# mySensors.net
KiCad netlist of a schematic drawn in EAGLE
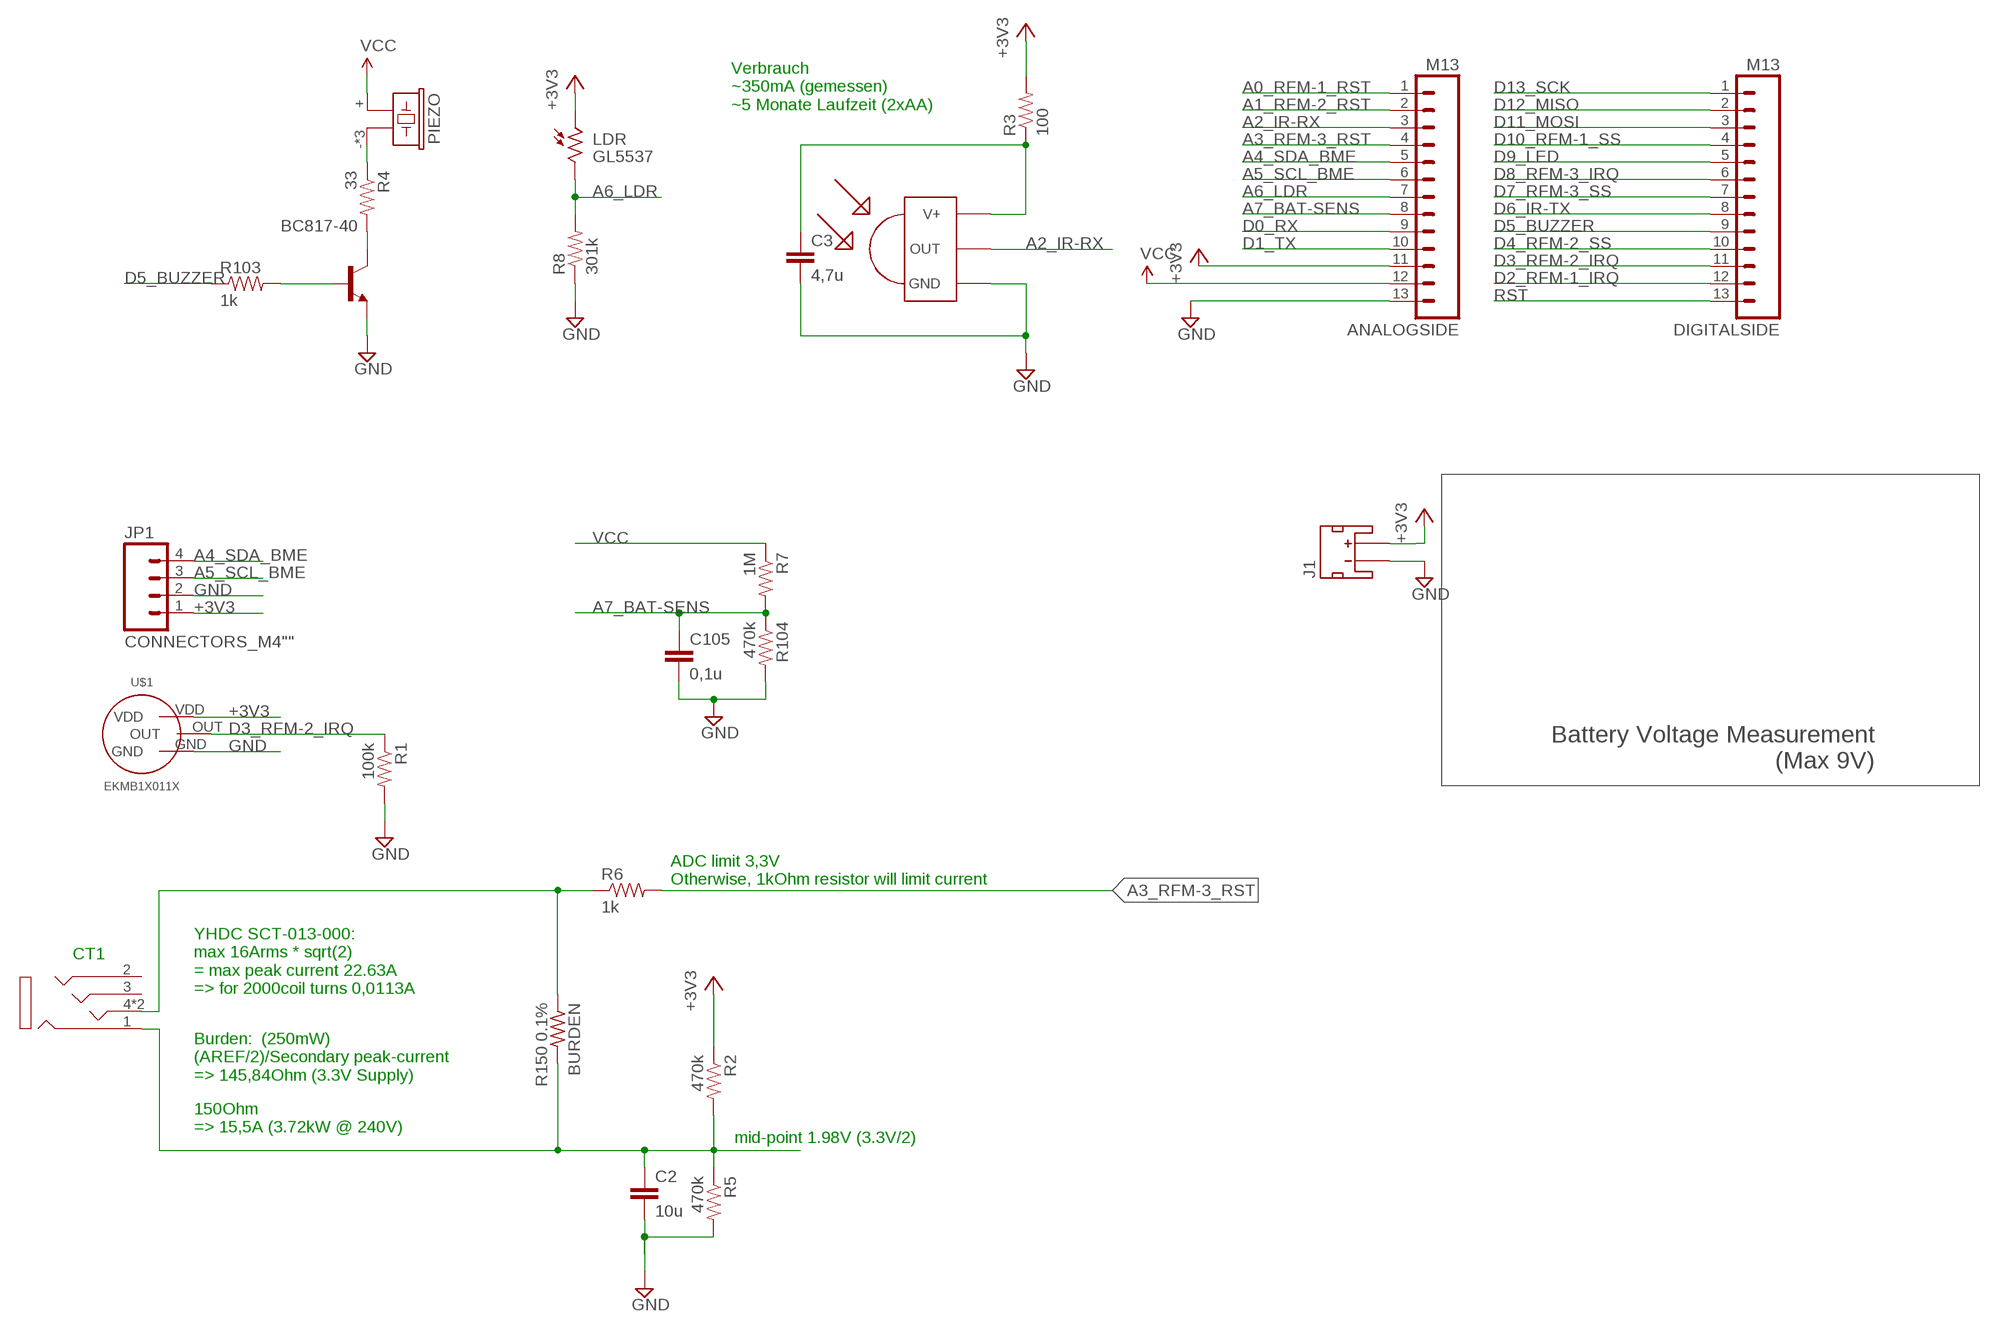
[diagram p0: schematic, sheet 1]

(export (version "E")
  (design (tool "Eeschema 10.0.6"))
  (components
    (comp (ref "ANALOGSIDE")
      (value "M13")
      (footprint "eagle-import:1X13")
      (libsource (lib "eagle-import") (part "M13"))
    )
    (comp (ref "BC817-40")
      (value "BC817-40-NPN-SOT23-BEC")
      (footprint "eagle-import:SOT23-BEC")
      (libsource (lib "eagle-import") (part "-NPN-SOT23-BECBC817-40"))
    )
    (comp (ref "BURDEN")
      (value "R150 0.1%")
      (footprint "eagle-import:R0805")
      (libsource (lib "eagle-import") (part "R-US_R0805"))
    )
    (comp (ref "C2")
      (value "10u")
      (footprint "eagle-import:0805-CAP")
      (libsource (lib "eagle-import") (part "CAP0805-CAP"))
    )
    (comp (ref "C3")
      (value "4,7u")
      (footprint "eagle-import:0805-CAP")
      (libsource (lib "eagle-import") (part "CAP0805-CAP"))
    )
    (comp (ref "C105")
      (value "0,1u")
      (footprint "eagle-import:0603-CAP")
      (libsource (lib "eagle-import") (part "CAP0603-CAP"))
    )
    (comp (ref "CT1")
      (value "1503_13")
      (footprint "eagle-import:1503-03")
      (libsource (lib "eagle-import") (part "1503_13"))
    )
    (comp (ref "DIGITALSIDE")
      (value "M13")
      (footprint "eagle-import:1X13")
      (libsource (lib "eagle-import") (part "M13"))
    )
    (comp (ref "IR-RX")
      (value "TSOP4836")
      (footprint "eagle-import:TSOP18XX")
      (libsource (lib "eagle-import") (part "TSOP4836"))
    )
    (comp (ref "J1")
      (value "JST_2MM_MALE")
      (footprint "eagle-import:JST-2-SMD")
      (libsource (lib "eagle-import") (part "JST_2MM_MALE"))
    )
    (comp (ref "JP1")
      (value "CONNECTORS_M4\"\"")
      (footprint "eagle-import:CONNECTORS_1X4")
      (libsource (lib "eagle-import") (part "CONNECTORS_M4{dblquote}{dblquote}"))
    )
    (comp (ref "LDR")
      (value "GL5537")
      (footprint "eagle-import:M9960")
      (libsource (lib "eagle-import") (part "M9960_11A"))
    )
    (comp (ref "PIEZO")
      (value "BUZZER-PIEZO_SMD")
      (footprint "eagle-import:BUZZER-PIEZO_SMD")
      (libsource (lib "eagle-import") (part "BUZZER-PIEZO_SMD"))
    )
    (comp (ref "R1")
      (value "100k")
      (footprint "eagle-import:0603-RES")
      (libsource (lib "eagle-import") (part "RESISTOR0603-RES"))
    )
    (comp (ref "R2")
      (value "470k")
      (footprint "eagle-import:0603-RES")
      (libsource (lib "eagle-import") (part "RESISTOR0603-RES"))
    )
    (comp (ref "R3")
      (value "100")
      (footprint "eagle-import:0603-RES")
      (libsource (lib "eagle-import") (part "RESISTOR0603-RES"))
    )
    (comp (ref "R4")
      (value "33")
      (footprint "eagle-import:0603-RES")
      (libsource (lib "eagle-import") (part "RESISTOR0603-RES"))
    )
    (comp (ref "R5")
      (value "470k")
      (footprint "eagle-import:0603-RES")
      (libsource (lib "eagle-import") (part "RESISTOR0603-RES"))
    )
    (comp (ref "R6")
      (value "1k")
      (footprint "eagle-import:0603-RES")
      (libsource (lib "eagle-import") (part "RESISTOR0603-RES"))
    )
    (comp (ref "R7")
      (value "1M")
      (footprint "eagle-import:0603-RES")
      (libsource (lib "eagle-import") (part "RESISTOR0603-RES"))
    )
    (comp (ref "R8")
      (value "301k")
      (footprint "eagle-import:0603-RES")
      (libsource (lib "eagle-import") (part "RESISTOR0603-RES"))
    )
    (comp (ref "R103")
      (value "1k")
      (footprint "eagle-import:0603-RES")
      (libsource (lib "eagle-import") (part "RESISTOR0603-RES"))
    )
    (comp (ref "R104")
      (value "470k")
      (footprint "eagle-import:0603-RES")
      (libsource (lib "eagle-import") (part "RESISTOR0603-RES"))
    )
    (comp (ref "U$1")
      (value "EKMB1X011X")
      (footprint "eagle-import:PIR-PANASONIC-VZ-WL-STANDARD")
      (libsource (lib "eagle-import") (part "EKMB1X011X"))
    )
  )
  (nets
    (net (code "1") (name "+3V3") (class "Default")
      (node (ref "ANALOGSIDE") (pin "11") (pinfunction "11_11") (pintype "passive"))
      (node (ref "J1") (pin "2") (pinfunction "+_2") (pintype "bidirectional"))
      (node (ref "JP1") (pin "1") (pinfunction "1_1") (pintype "passive"))
      (node (ref "LDR") (pin "1") (pinfunction "1_1") (pintype "passive"))
      (node (ref "R2") (pin "1") (pinfunction "1_1") (pintype "passive"))
      (node (ref "R3") (pin "2") (pinfunction "2_2") (pintype "passive"))
      (node (ref "U$1") (pin "VDD") (pinfunction "VDD_VDD") (pintype "bidirectional"))
    )
    (net (code "2") (name "/A0_RFM-1_RST") (class "Default")
      (node (ref "ANALOGSIDE") (pin "1") (pinfunction "1_1") (pintype "passive"))
    )
    (net (code "3") (name "/A1_RFM-2_RST") (class "Default")
      (node (ref "ANALOGSIDE") (pin "2") (pinfunction "2_2") (pintype "passive"))
    )
    (net (code "4") (name "/A2_IR-RX") (class "Default")
      (node (ref "ANALOGSIDE") (pin "3") (pinfunction "3_3") (pintype "passive"))
      (node (ref "IR-RX") (pin "OUT") (pinfunction "OUT_OUT") (pintype "bidirectional"))
    )
    (net (code "5") (name "/A4_SDA_BME") (class "Default")
      (node (ref "ANALOGSIDE") (pin "5") (pinfunction "5_5") (pintype "passive"))
      (node (ref "JP1") (pin "4") (pinfunction "4_4") (pintype "passive"))
    )
    (net (code "6") (name "/A5_SCL_BME") (class "Default")
      (node (ref "ANALOGSIDE") (pin "6") (pinfunction "6_6") (pintype "passive"))
      (node (ref "JP1") (pin "3") (pinfunction "3_3") (pintype "passive"))
    )
    (net (code "7") (name "/A6_LDR") (class "Default")
      (node (ref "ANALOGSIDE") (pin "7") (pinfunction "7_7") (pintype "passive"))
      (node (ref "LDR") (pin "2") (pinfunction "2_2") (pintype "passive"))
      (node (ref "R8") (pin "2") (pinfunction "2_2") (pintype "passive"))
    )
    (net (code "8") (name "/A7_BAT-SENS") (class "Default")
      (node (ref "ANALOGSIDE") (pin "8") (pinfunction "8_8") (pintype "passive"))
      (node (ref "C105") (pin "1") (pinfunction "1_1") (pintype "passive"))
      (node (ref "R104") (pin "1") (pinfunction "1_1") (pintype "passive"))
      (node (ref "R7") (pin "2") (pinfunction "2_2") (pintype "passive"))
    )
    (net (code "9") (name "/D0_RX") (class "Default")
      (node (ref "ANALOGSIDE") (pin "9") (pinfunction "9_9") (pintype "passive"))
    )
    (net (code "10") (name "/D1_TX") (class "Default")
      (node (ref "ANALOGSIDE") (pin "10") (pinfunction "10_10") (pintype "passive"))
    )
    (net (code "11") (name "/D2_RFM-1_IRQ") (class "Default")
      (node (ref "DIGITALSIDE") (pin "12") (pinfunction "12_12") (pintype "passive"))
    )
    (net (code "12") (name "/D3_RFM-2_IRQ") (class "Default")
      (node (ref "DIGITALSIDE") (pin "11") (pinfunction "11_11") (pintype "passive"))
      (node (ref "R1") (pin "1") (pinfunction "1_1") (pintype "passive"))
      (node (ref "U$1") (pin "OUT") (pinfunction "OUT_OUT") (pintype "bidirectional"))
    )
    (net (code "13") (name "/D4_RFM-2_SS") (class "Default")
      (node (ref "DIGITALSIDE") (pin "10") (pinfunction "10_10") (pintype "passive"))
    )
    (net (code "14") (name "/D5_BUZZER") (class "Default")
      (node (ref "DIGITALSIDE") (pin "9") (pinfunction "9_9") (pintype "passive"))
      (node (ref "R103") (pin "1") (pinfunction "1_1") (pintype "passive"))
    )
    (net (code "15") (name "/D6_IR-TX") (class "Default")
      (node (ref "DIGITALSIDE") (pin "8") (pinfunction "8_8") (pintype "passive"))
    )
    (net (code "16") (name "/D7_RFM-3_SS") (class "Default")
      (node (ref "DIGITALSIDE") (pin "7") (pinfunction "7_7") (pintype "passive"))
    )
    (net (code "17") (name "/D8_RFM-3_IRQ") (class "Default")
      (node (ref "DIGITALSIDE") (pin "6") (pinfunction "6_6") (pintype "passive"))
    )
    (net (code "18") (name "/D9_LED") (class "Default")
      (node (ref "DIGITALSIDE") (pin "5") (pinfunction "5_5") (pintype "passive"))
    )
    (net (code "19") (name "/D10_RFM-1_SS") (class "Default")
      (node (ref "DIGITALSIDE") (pin "4") (pinfunction "4_4") (pintype "passive"))
    )
    (net (code "20") (name "/D11_MOSI") (class "Default")
      (node (ref "DIGITALSIDE") (pin "3") (pinfunction "3_3") (pintype "passive"))
    )
    (net (code "21") (name "/D12_MISO") (class "Default")
      (node (ref "DIGITALSIDE") (pin "2") (pinfunction "2_2") (pintype "passive"))
    )
    (net (code "22") (name "/D13_SCK") (class "Default")
      (node (ref "DIGITALSIDE") (pin "1") (pinfunction "1_1") (pintype "passive"))
    )
    (net (code "23") (name "/RST") (class "Default")
      (node (ref "DIGITALSIDE") (pin "13") (pinfunction "13_13") (pintype "passive"))
    )
    (net (code "24") (name "A3_RFM-3_RST") (class "Default")
      (node (ref "ANALOGSIDE") (pin "4") (pinfunction "4_4") (pintype "passive"))
      (node (ref "R6") (pin "2") (pinfunction "2_2") (pintype "passive"))
    )
    (net (code "25") (name "GND") (class "Default")
      (node (ref "ANALOGSIDE") (pin "13") (pinfunction "13_13") (pintype "passive"))
      (node (ref "BC817-40") (pin "E") (pinfunction "E_E") (pintype "passive"))
      (node (ref "C105") (pin "2") (pinfunction "2_2") (pintype "passive"))
      (node (ref "C2") (pin "2") (pinfunction "2_2") (pintype "passive"))
      (node (ref "C3") (pin "2") (pinfunction "2_2") (pintype "passive"))
      (node (ref "IR-RX") (pin "GND") (pinfunction "GND_GND") (pintype "bidirectional"))
      (node (ref "J1") (pin "1") (pinfunction "-_1") (pintype "bidirectional"))
      (node (ref "JP1") (pin "2") (pinfunction "2_2") (pintype "passive"))
      (node (ref "R1") (pin "2") (pinfunction "2_2") (pintype "passive"))
      (node (ref "R104") (pin "2") (pinfunction "2_2") (pintype "passive"))
      (node (ref "R5") (pin "2") (pinfunction "2_2") (pintype "passive"))
      (node (ref "R8") (pin "1") (pinfunction "1_1") (pintype "passive"))
      (node (ref "U$1") (pin "GND") (pinfunction "GND_GND") (pintype "bidirectional"))
    )
    (net (code "26") (name "Net-(BC817-40-PadB)") (class "Default")
      (node (ref "BC817-40") (pin "B") (pinfunction "B_B") (pintype "passive"))
      (node (ref "R103") (pin "2") (pinfunction "2_2") (pintype "passive"))
    )
    (net (code "27") (name "Net-(BC817-40-PadC)") (class "Default")
      (node (ref "BC817-40") (pin "C") (pinfunction "C_C") (pintype "passive"))
      (node (ref "R4") (pin "2") (pinfunction "2_2") (pintype "passive"))
    )
    (net (code "28") (name "Net-(BURDEN-Pad1)") (class "Default")
      (node (ref "BURDEN") (pin "1") (pinfunction "1_1") (pintype "passive"))
      (node (ref "CT1") (pin "4") (pinfunction "4_4") (pintype "bidirectional"))
      (node (ref "CT1") (pin "4-2") (pinfunction "4_4-2") (pintype "bidirectional"))
      (node (ref "R6") (pin "1") (pinfunction "1_1") (pintype "passive"))
    )
    (net (code "29") (name "Net-(BURDEN-Pad2)") (class "Default")
      (node (ref "BURDEN") (pin "2") (pinfunction "2_2") (pintype "passive"))
      (node (ref "C2") (pin "1") (pinfunction "1_1") (pintype "passive"))
      (node (ref "CT1") (pin "1") (pinfunction "1_1") (pintype "bidirectional"))
      (node (ref "R2") (pin "2") (pinfunction "2_2") (pintype "passive"))
      (node (ref "R5") (pin "1") (pinfunction "1_1") (pintype "passive"))
    )
    (net (code "30") (name "Net-(IR-RX-V+)") (class "Default")
      (node (ref "C3") (pin "1") (pinfunction "1_1") (pintype "passive"))
      (node (ref "IR-RX") (pin "VCC") (pinfunction "V+_VCC") (pintype "bidirectional"))
      (node (ref "R3") (pin "1") (pinfunction "1_1") (pintype "passive"))
    )
    (net (code "31") (name "Net-(PIEZO-2-Pad-)") (class "Default")
      (node (ref "PIEZO") (pin "-") (pinfunction "2_-") (pintype "passive"))
      (node (ref "PIEZO") (pin "DUMMY") (pinfunction "2_DUMMY") (pintype "passive"))
      (node (ref "PIEZO") (pin "DUMMY1") (pinfunction "2_DUMMY1") (pintype "passive"))
      (node (ref "R4") (pin "1") (pinfunction "1_1") (pintype "passive"))
    )
    (net (code "32") (name "VCC") (class "Default")
      (node (ref "ANALOGSIDE") (pin "12") (pinfunction "12_12") (pintype "passive"))
      (node (ref "PIEZO") (pin "+") (pinfunction "1_+") (pintype "passive"))
      (node (ref "R7") (pin "1") (pinfunction "1_1") (pintype "passive"))
    )
    (net (code "33") (name "unconnected-(CT1-Pad2)") (class "Default")
      (node (ref "CT1") (pin "2") (pinfunction "2_2") (pintype "bidirectional"))
    )
    (net (code "34") (name "unconnected-(CT1-Pad3)") (class "Default")
      (node (ref "CT1") (pin "3") (pinfunction "3_3") (pintype "bidirectional"))
    )
    (net (code "35") (name "unconnected-(J1-PAD1-PadNC1)") (class "Default")
      (node (ref "J1") (pin "NC1") (pinfunction "PAD1_NC1") (pintype "bidirectional"))
    )
    (net (code "36") (name "unconnected-(J1-PAD2-PadNC2)") (class "Default")
      (node (ref "J1") (pin "NC2") (pinfunction "PAD2_NC2") (pintype "bidirectional"))
    )
  )
)
